# subpar-igbt-driver.net
KiCad netlist of a schematic drawn in EAGLE
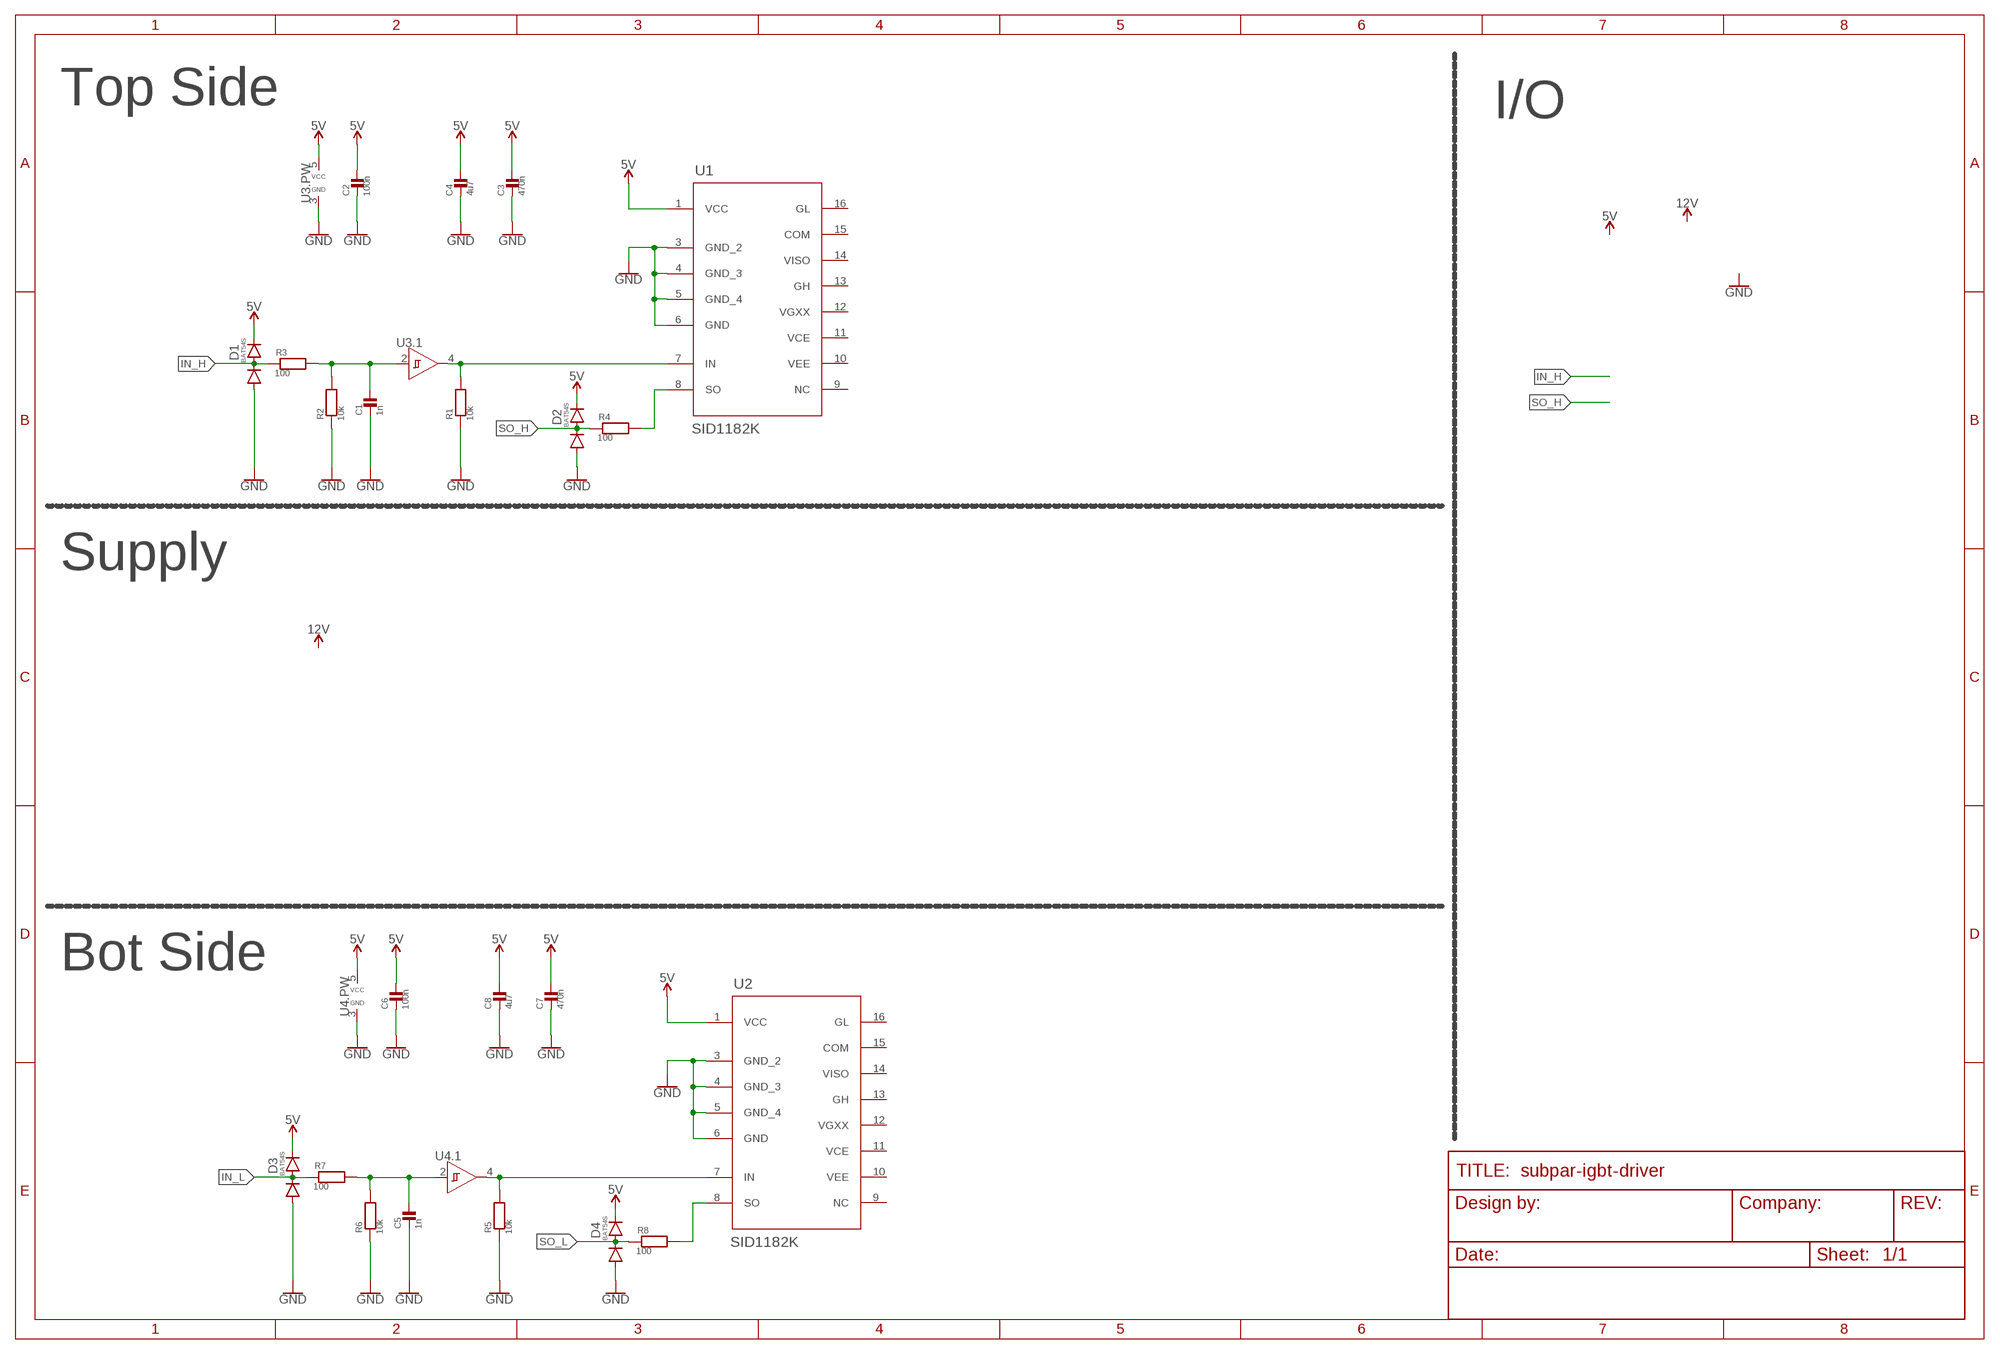
[diagram p0: schematic, sheet 1]

(export (version "E")
  (design (tool "Eeschema 10.0.6"))
  (components
    (comp (ref "C1")
      (value "1n")
      (footprint "eagle-import:0603_WAVE")
      (libsource (lib "eagle-import") (part "MLCC0603"))
    )
    (comp (ref "C2")
      (value "100n")
      (footprint "eagle-import:0603_WAVE")
      (libsource (lib "eagle-import") (part "MLCC0603"))
    )
    (comp (ref "C3")
      (value "470n")
      (footprint "eagle-import:0603_WAVE")
      (libsource (lib "eagle-import") (part "MLCC0603"))
    )
    (comp (ref "C4")
      (value "4u7")
      (footprint "eagle-import:0603_WAVE")
      (libsource (lib "eagle-import") (part "MLCC0603"))
    )
    (comp (ref "C5")
      (value "1n")
      (footprint "eagle-import:0603_WAVE")
      (libsource (lib "eagle-import") (part "MLCC0603"))
    )
    (comp (ref "C6")
      (value "100n")
      (footprint "eagle-import:0603_WAVE")
      (libsource (lib "eagle-import") (part "MLCC0603"))
    )
    (comp (ref "C7")
      (value "470n")
      (footprint "eagle-import:0603_WAVE")
      (libsource (lib "eagle-import") (part "MLCC0603"))
    )
    (comp (ref "C8")
      (value "4u7")
      (footprint "eagle-import:0603_WAVE")
      (libsource (lib "eagle-import") (part "MLCC0603"))
    )
    (comp (ref "D1")
      (value "BAT54S")
      (footprint "eagle-import:SOT-23-3")
      (libsource (lib "eagle-import") (part "BAT54S"))
    )
    (comp (ref "D2")
      (value "BAT54S")
      (footprint "eagle-import:SOT-23-3")
      (libsource (lib "eagle-import") (part "BAT54S"))
    )
    (comp (ref "D3")
      (value "BAT54S")
      (footprint "eagle-import:SOT-23-3")
      (libsource (lib "eagle-import") (part "BAT54S"))
    )
    (comp (ref "D4")
      (value "BAT54S")
      (footprint "eagle-import:SOT-23-3")
      (libsource (lib "eagle-import") (part "BAT54S"))
    )
    (comp (ref "R1")
      (value "10k")
      (footprint "eagle-import:0603_WAVE")
      (libsource (lib "eagle-import") (part "RESISTOR0603"))
    )
    (comp (ref "R2")
      (value "10k")
      (footprint "eagle-import:0603_WAVE")
      (libsource (lib "eagle-import") (part "RESISTOR0603"))
    )
    (comp (ref "R3")
      (value "100")
      (footprint "eagle-import:0603_WAVE")
      (libsource (lib "eagle-import") (part "RESISTOR0603"))
    )
    (comp (ref "R4")
      (value "100")
      (footprint "eagle-import:0603_WAVE")
      (libsource (lib "eagle-import") (part "RESISTOR0603"))
    )
    (comp (ref "R5")
      (value "10k")
      (footprint "eagle-import:0603_WAVE")
      (libsource (lib "eagle-import") (part "RESISTOR0603"))
    )
    (comp (ref "R6")
      (value "10k")
      (footprint "eagle-import:0603_WAVE")
      (libsource (lib "eagle-import") (part "RESISTOR0603"))
    )
    (comp (ref "R7")
      (value "100")
      (footprint "eagle-import:0603_WAVE")
      (libsource (lib "eagle-import") (part "RESISTOR0603"))
    )
    (comp (ref "R8")
      (value "100")
      (footprint "eagle-import:0603_WAVE")
      (libsource (lib "eagle-import") (part "RESISTOR0603"))
    )
    (comp (ref "U1")
      (value "SID1182K")
      (footprint "eagle-import:ESOP-R16B")
      (libsource (lib "eagle-import") (part "SID1182K"))
    )
    (comp (ref "U2")
      (value "SID1182K")
      (footprint "eagle-import:ESOP-R16B")
      (libsource (lib "eagle-import") (part "SID1182K"))
    )
    (comp (ref "U3")
      (value "74LVC1G17")
      (footprint "eagle-import:SC70-5")
      (libsource (lib "eagle-import") (part "74LVC1G17"))
    )
    (comp (ref "U4")
      (value "74LVC1G17")
      (footprint "eagle-import:SC70-5")
      (libsource (lib "eagle-import") (part "74LVC1G17"))
    )
  )
  (nets
    (net (code "1") (name "5V") (class "Default")
      (node (ref "C2") (pin "P$1") (pinfunction "P$1_P$1") (pintype "bidirectional"))
      (node (ref "C3") (pin "P$1") (pinfunction "P$1_P$1") (pintype "bidirectional"))
      (node (ref "C4") (pin "P$1") (pinfunction "P$1_P$1") (pintype "bidirectional"))
      (node (ref "C6") (pin "P$1") (pinfunction "P$1_P$1") (pintype "bidirectional"))
      (node (ref "C7") (pin "P$1") (pinfunction "P$1_P$1") (pintype "bidirectional"))
      (node (ref "C8") (pin "P$1") (pinfunction "P$1_P$1") (pintype "bidirectional"))
      (node (ref "D1") (pin "P$2") (pinfunction "2_P$2") (pintype "bidirectional"))
      (node (ref "D2") (pin "P$2") (pinfunction "2_P$2") (pintype "bidirectional"))
      (node (ref "D3") (pin "P$2") (pinfunction "2_P$2") (pintype "bidirectional"))
      (node (ref "D4") (pin "P$2") (pinfunction "2_P$2") (pintype "bidirectional"))
      (node (ref "U1") (pin "1") (pinfunction "VCC_1") (pintype "passive"))
      (node (ref "U2") (pin "1") (pinfunction "VCC_1") (pintype "passive"))
      (node (ref "U3") (pin "5") (pinfunction "VCC_5") (pintype "bidirectional"))
      (node (ref "U4") (pin "5") (pinfunction "VCC_5") (pintype "bidirectional"))
    )
    (net (code "3") (name "GND") (class "Default")
      (node (ref "C1") (pin "P$2") (pinfunction "P$2_P$2") (pintype "bidirectional"))
      (node (ref "C2") (pin "P$2") (pinfunction "P$2_P$2") (pintype "bidirectional"))
      (node (ref "C3") (pin "P$2") (pinfunction "P$2_P$2") (pintype "bidirectional"))
      (node (ref "C4") (pin "P$2") (pinfunction "P$2_P$2") (pintype "bidirectional"))
      (node (ref "C5") (pin "P$2") (pinfunction "P$2_P$2") (pintype "bidirectional"))
      (node (ref "C6") (pin "P$2") (pinfunction "P$2_P$2") (pintype "bidirectional"))
      (node (ref "C7") (pin "P$2") (pinfunction "P$2_P$2") (pintype "bidirectional"))
      (node (ref "C8") (pin "P$2") (pinfunction "P$2_P$2") (pintype "bidirectional"))
      (node (ref "D1") (pin "P$1") (pinfunction "1_P$1") (pintype "bidirectional"))
      (node (ref "D2") (pin "P$1") (pinfunction "1_P$1") (pintype "bidirectional"))
      (node (ref "D3") (pin "P$1") (pinfunction "1_P$1") (pintype "bidirectional"))
      (node (ref "D4") (pin "P$1") (pinfunction "1_P$1") (pintype "bidirectional"))
      (node (ref "R1") (pin "P$1") (pinfunction "P$1_P$1") (pintype "bidirectional"))
      (node (ref "R2") (pin "P$1") (pinfunction "P$1_P$1") (pintype "bidirectional"))
      (node (ref "R5") (pin "P$1") (pinfunction "P$1_P$1") (pintype "bidirectional"))
      (node (ref "R6") (pin "P$1") (pinfunction "P$1_P$1") (pintype "bidirectional"))
      (node (ref "U1") (pin "3") (pinfunction "GND_2_3") (pintype "passive"))
      (node (ref "U1") (pin "4") (pinfunction "GND_3_4") (pintype "passive"))
      (node (ref "U1") (pin "5") (pinfunction "GND_4_5") (pintype "passive"))
      (node (ref "U1") (pin "6") (pinfunction "GND_6") (pintype "passive"))
      (node (ref "U2") (pin "3") (pinfunction "GND_2_3") (pintype "passive"))
      (node (ref "U2") (pin "4") (pinfunction "GND_3_4") (pintype "passive"))
      (node (ref "U2") (pin "5") (pinfunction "GND_4_5") (pintype "passive"))
      (node (ref "U2") (pin "6") (pinfunction "GND_6") (pintype "passive"))
      (node (ref "U3") (pin "3") (pinfunction "GND_3") (pintype "bidirectional"))
      (node (ref "U4") (pin "3") (pinfunction "GND_3") (pintype "bidirectional"))
    )
    (net (code "4") (name "IN_H") (class "Default")
      (node (ref "D1") (pin "P$3") (pinfunction "3_P$3") (pintype "bidirectional"))
      (node (ref "R3") (pin "P$1") (pinfunction "P$1_P$1") (pintype "bidirectional"))
    )
    (net (code "5") (name "IN_L") (class "Default")
      (node (ref "D3") (pin "P$3") (pinfunction "3_P$3") (pintype "bidirectional"))
      (node (ref "R7") (pin "P$1") (pinfunction "P$1_P$1") (pintype "bidirectional"))
    )
    (net (code "6") (name "Net-(U1-IN)") (class "Default")
      (node (ref "R1") (pin "P$2") (pinfunction "P$2_P$2") (pintype "bidirectional"))
      (node (ref "U1") (pin "7") (pinfunction "IN_7") (pintype "passive"))
      (node (ref "U3") (pin "4") (pinfunction "Y_4") (pintype "output"))
    )
    (net (code "7") (name "Net-(U1-SO)") (class "Default")
      (node (ref "R4") (pin "P$2") (pinfunction "P$2_P$2") (pintype "bidirectional"))
      (node (ref "U1") (pin "8") (pinfunction "SO_8") (pintype "passive"))
    )
    (net (code "8") (name "Net-(U2-IN)") (class "Default")
      (node (ref "R5") (pin "P$2") (pinfunction "P$2_P$2") (pintype "bidirectional"))
      (node (ref "U2") (pin "7") (pinfunction "IN_7") (pintype "passive"))
      (node (ref "U4") (pin "4") (pinfunction "Y_4") (pintype "output"))
    )
    (net (code "9") (name "Net-(U2-SO)") (class "Default")
      (node (ref "R8") (pin "P$2") (pinfunction "P$2_P$2") (pintype "bidirectional"))
      (node (ref "U2") (pin "8") (pinfunction "SO_8") (pintype "passive"))
    )
    (net (code "10") (name "Net-(U3A-A)") (class "Default")
      (node (ref "C1") (pin "P$1") (pinfunction "P$1_P$1") (pintype "bidirectional"))
      (node (ref "R2") (pin "P$2") (pinfunction "P$2_P$2") (pintype "bidirectional"))
      (node (ref "R3") (pin "P$2") (pinfunction "P$2_P$2") (pintype "bidirectional"))
      (node (ref "U3") (pin "2") (pinfunction "A_2") (pintype "input"))
    )
    (net (code "11") (name "Net-(U4A-A)") (class "Default")
      (node (ref "C5") (pin "P$1") (pinfunction "P$1_P$1") (pintype "bidirectional"))
      (node (ref "R6") (pin "P$2") (pinfunction "P$2_P$2") (pintype "bidirectional"))
      (node (ref "R7") (pin "P$2") (pinfunction "P$2_P$2") (pintype "bidirectional"))
      (node (ref "U4") (pin "2") (pinfunction "A_2") (pintype "input"))
    )
    (net (code "12") (name "SO_H") (class "Default")
      (node (ref "D2") (pin "P$3") (pinfunction "3_P$3") (pintype "bidirectional"))
      (node (ref "R4") (pin "P$1") (pinfunction "P$1_P$1") (pintype "bidirectional"))
    )
    (net (code "13") (name "SO_L") (class "Default")
      (node (ref "D4") (pin "P$3") (pinfunction "3_P$3") (pintype "bidirectional"))
      (node (ref "R8") (pin "P$1") (pinfunction "P$1_P$1") (pintype "bidirectional"))
    )
    (net (code "14") (name "unconnected-(U1-COM-Pad15)") (class "Default")
      (node (ref "U1") (pin "15") (pinfunction "COM_15") (pintype "passive"))
    )
    (net (code "15") (name "unconnected-(U1-GH-Pad13)") (class "Default")
      (node (ref "U1") (pin "13") (pinfunction "GH_13") (pintype "passive"))
    )
    (net (code "16") (name "unconnected-(U1-GL-Pad16)") (class "Default")
      (node (ref "U1") (pin "16") (pinfunction "GL_16") (pintype "passive"))
    )
    (net (code "17") (name "unconnected-(U1-NC-Pad9)") (class "Default")
      (node (ref "U1") (pin "9") (pinfunction "NC_9") (pintype "passive"))
    )
    (net (code "18") (name "unconnected-(U1-VCE-Pad11)") (class "Default")
      (node (ref "U1") (pin "11") (pinfunction "VCE_11") (pintype "passive"))
    )
    (net (code "19") (name "unconnected-(U1-VEE-Pad10)") (class "Default")
      (node (ref "U1") (pin "10") (pinfunction "VEE_10") (pintype "passive"))
    )
    (net (code "20") (name "unconnected-(U1-VGXX-Pad12)") (class "Default")
      (node (ref "U1") (pin "12") (pinfunction "VGXX_12") (pintype "passive"))
    )
    (net (code "21") (name "unconnected-(U1-VISO-Pad14)") (class "Default")
      (node (ref "U1") (pin "14") (pinfunction "VISO_14") (pintype "passive"))
    )
    (net (code "22") (name "unconnected-(U2-COM-Pad15)") (class "Default")
      (node (ref "U2") (pin "15") (pinfunction "COM_15") (pintype "passive"))
    )
    (net (code "23") (name "unconnected-(U2-GH-Pad13)") (class "Default")
      (node (ref "U2") (pin "13") (pinfunction "GH_13") (pintype "passive"))
    )
    (net (code "24") (name "unconnected-(U2-GL-Pad16)") (class "Default")
      (node (ref "U2") (pin "16") (pinfunction "GL_16") (pintype "passive"))
    )
    (net (code "25") (name "unconnected-(U2-NC-Pad9)") (class "Default")
      (node (ref "U2") (pin "9") (pinfunction "NC_9") (pintype "passive"))
    )
    (net (code "26") (name "unconnected-(U2-VCE-Pad11)") (class "Default")
      (node (ref "U2") (pin "11") (pinfunction "VCE_11") (pintype "passive"))
    )
    (net (code "27") (name "unconnected-(U2-VEE-Pad10)") (class "Default")
      (node (ref "U2") (pin "10") (pinfunction "VEE_10") (pintype "passive"))
    )
    (net (code "28") (name "unconnected-(U2-VGXX-Pad12)") (class "Default")
      (node (ref "U2") (pin "12") (pinfunction "VGXX_12") (pintype "passive"))
    )
    (net (code "29") (name "unconnected-(U2-VISO-Pad14)") (class "Default")
      (node (ref "U2") (pin "14") (pinfunction "VISO_14") (pintype "passive"))
    )
  )
)
